# beeper.net
KiCad netlist of a schematic drawn in EAGLE
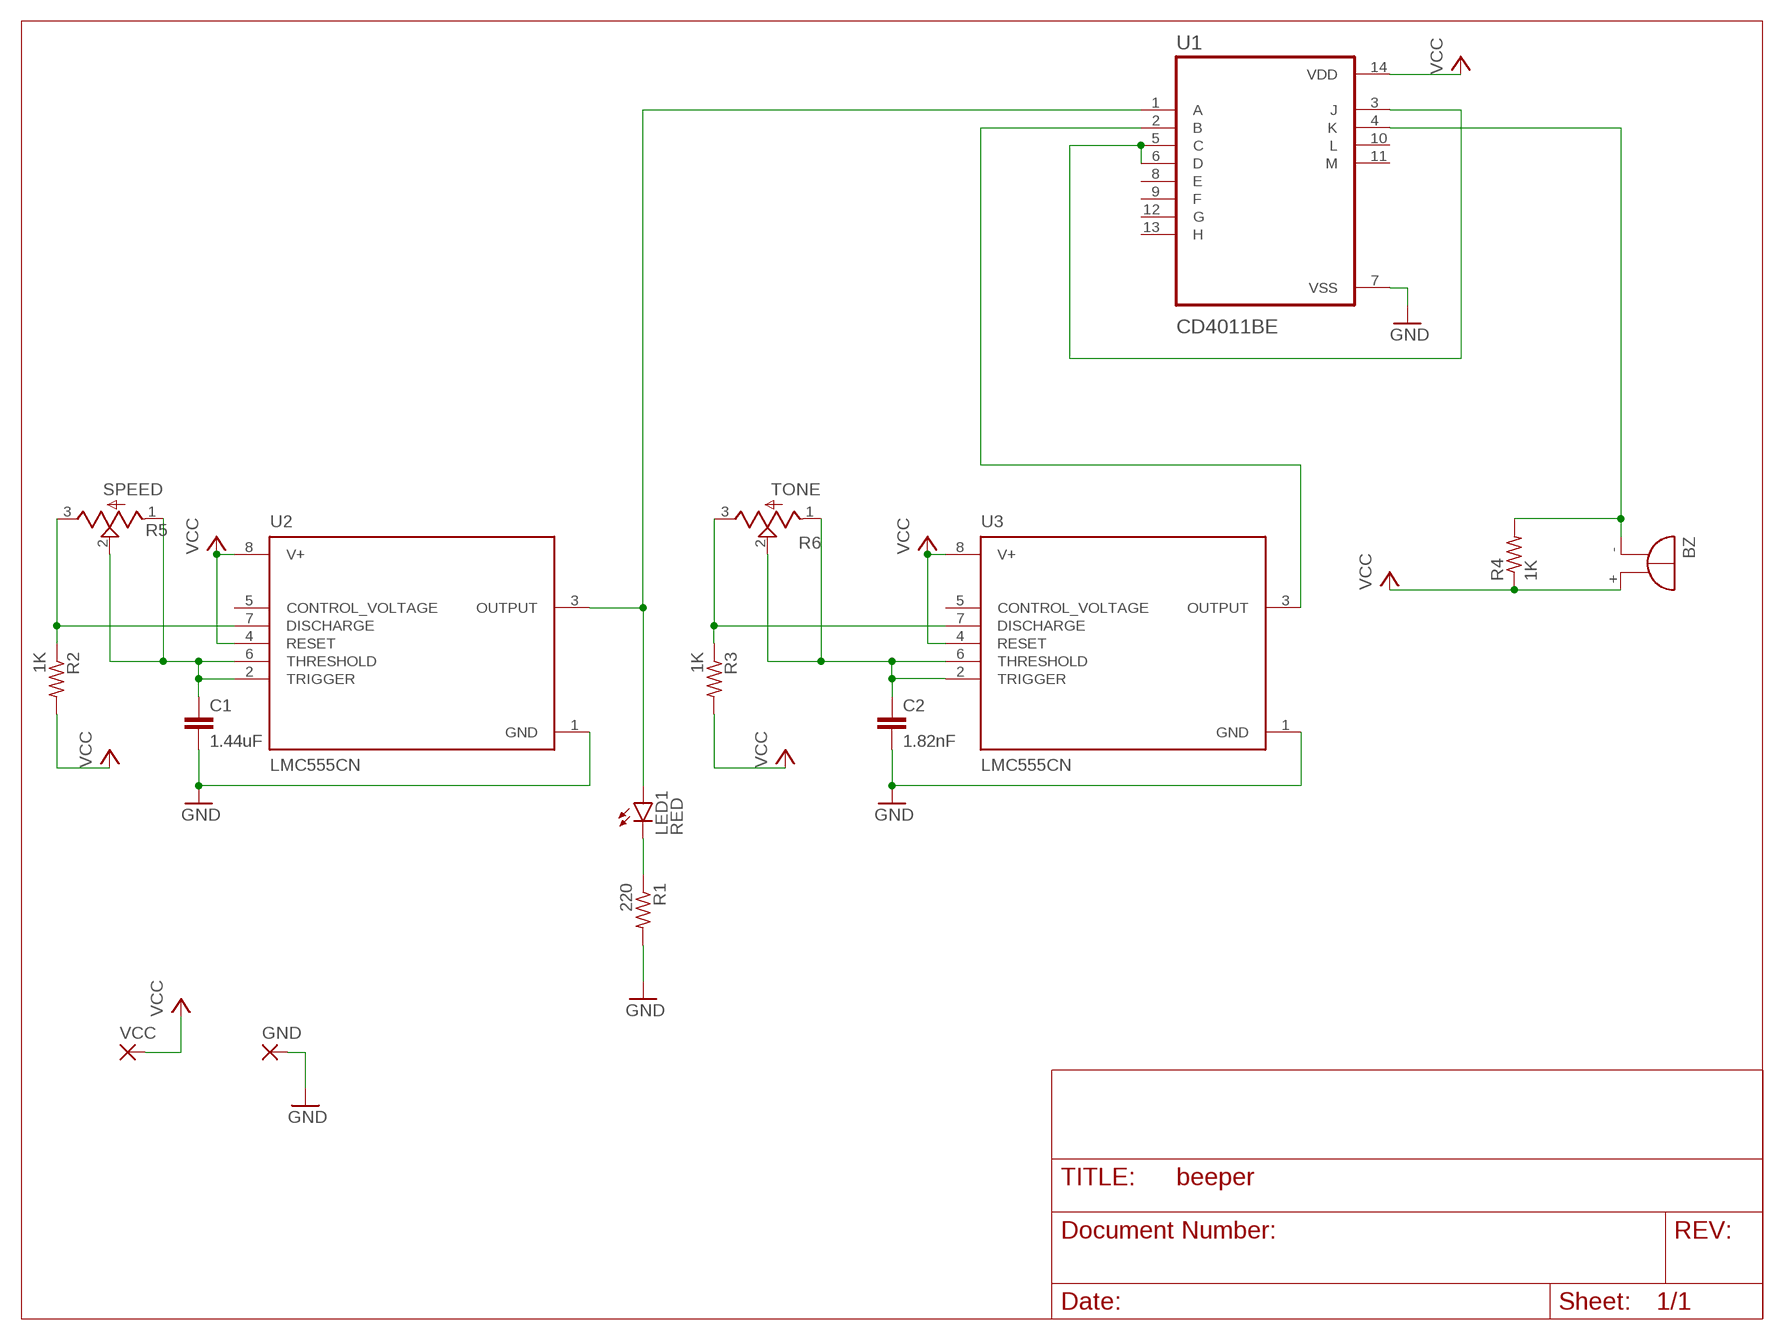
[diagram p0: schematic, sheet 1]

(export (version "E")
  (design (tool "Eeschema 10.0.6"))
  (components
    (comp (ref "BZ")
      (value "F/QMBIII")
      (footprint "eagle-import:F_QMBIII")
      (fields
        (field (name "MF") "PROJECTS UNLIMITED")
        (field (name "MPN") "AI-1440-TWT-12V-R")
        (field (name "OC_NEWARK") "47W0784")
      )
      (libsource (lib "eagle-import") (part "F/QMBIII"))
    )
    (comp (ref "C1")
      (value "1.44uF")
      (footprint "eagle-import:C2.5-3")
      (fields (field (name "MF") "MULTICOMP PRO") (field (name "MPN") "MPMPP250W15J0N200"))
      (libsource (lib "eagle-import") (part "C2,5-3"))
    )
    (comp (ref "C2")
      (value "1.82nF")
      (footprint "eagle-import:C2.5-3")
      (fields (field (name "MF") "TDK") (field (name "MPN") "FA26C0G2J182JNU00"))
      (libsource (lib "eagle-import") (part "C2,5-3"))
    )
    (comp (ref "GND")
      (value "SMD2")
      (footprint "eagle-import:SMD1,27-2,54")
      (libsource (lib "eagle-import") (part "SMD2"))
    )
    (comp (ref "LED1")
      (value "RED")
      (footprint "eagle-import:LED3MM")
      (fields
        (field (name "MF") "VISHAY SEMICONDUCTOR")
        (field (name "MF_1") "VISHAY")
        (field (name "MPN") "TLLR4400")
      )
      (libsource (lib "eagle-import") (part "TLLR4400"))
    )
    (comp (ref "R1")
      (value "220")
      (footprint "eagle-import:0204_7")
      (fields (field (name "MF") "MULTICOMP PRO") (field (name "MPN") "MCF 0.25W 220R"))
      (libsource (lib "eagle-import") (part "R-US_0204/7"))
    )
    (comp (ref "R2")
      (value "1K")
      (footprint "eagle-import:0204_7")
      (fields (field (name "MF") "MULTICOMP PRO") (field (name "MPN") "MP006904"))
      (libsource (lib "eagle-import") (part "R-US_0204/7"))
    )
    (comp (ref "R3")
      (value "1K")
      (footprint "eagle-import:0204_7")
      (fields (field (name "MF") "MULTICOMP PRO") (field (name "MPN") "MP006904"))
      (libsource (lib "eagle-import") (part "R-US_0204/7"))
    )
    (comp (ref "R4")
      (value "1K")
      (footprint "eagle-import:0204_7")
      (fields (field (name "MF") "MULTICOMP PRO") (field (name "MPN") "MP006904"))
      (libsource (lib "eagle-import") (part "R-US_0204/7"))
    )
    (comp (ref "R5")
      (value "SPEED")
      (footprint "eagle-import:TO250P760H635-3_PV12P105A01B00")
      (fields
        (field (name "MF") "Murata Electronics")
        (field (name "MP") "PV12P105A01B00")
        (field (name "MF_1") "BOURNS")
      )
      (libsource (lib "eagle-import") (part "PV12P105A01B00"))
    )
    (comp (ref "R6")
      (value "TONE")
      (footprint "eagle-import:TO250P760H635-3_PV12P105A01B00")
      (fields
        (field (name "MF") "Murata Electronics")
        (field (name "MP") "PV12P105A01B00")
        (field (name "MF_1") "BOURNS")
      )
      (libsource (lib "eagle-import") (part "PV12P105A01B00"))
    )
    (comp (ref "U1")
      (value "CD4011BE")
      (footprint "eagle-import:DIP794W45P254L1969H508Q14")
      (fields (field (name "MF") "Texas Instruments") (field (name "MF_1") "TEXAS INSTRUMENTS"))
      (libsource (lib "eagle-import") (part "CD4011BE"))
    )
    (comp (ref "U2")
      (value "LMC555CN")
      (footprint "eagle-import:DIP794W45P254L959H508Q8")
      (fields
        (field (name "MF") "Texas Instruments")
        (field (name "MF_1") "ONSEMI")
        (field (name "MPN") "LM555CN")
      )
      (libsource (lib "eagle-import") (part "LMC555CN"))
    )
    (comp (ref "U3")
      (value "LMC555CN")
      (footprint "eagle-import:DIP794W45P254L959H508Q8")
      (fields
        (field (name "MF") "Texas Instruments")
        (field (name "MF_1") "ONSEMI")
        (field (name "MPN") "LM555CN")
      )
      (libsource (lib "eagle-import") (part "LMC555CN"))
    )
    (comp (ref "VCC")
      (value "SMD2")
      (footprint "eagle-import:SMD1,27-2,54")
      (libsource (lib "eagle-import") (part "SMD2"))
    )
  )
  (nets
    (net (code "1") (name "GND") (class "Default")
      (node (ref "C1") (pin "2") (pinfunction "2_2") (pintype "passive"))
      (node (ref "C2") (pin "2") (pinfunction "2_2") (pintype "passive"))
      (node (ref "GND") (pin "1") (pinfunction "P_1") (pintype "passive"))
      (node (ref "R1") (pin "2") (pinfunction "2_2") (pintype "passive"))
      (node (ref "U1") (pin "7") (pinfunction "VSS_7") (pintype "power_in"))
      (node (ref "U2") (pin "1") (pinfunction "GND_1") (pintype "power_in"))
      (node (ref "U3") (pin "1") (pinfunction "GND_1") (pintype "power_in"))
    )
    (net (code "2") (name "Net-(BZ-+)") (class "Default")
      (node (ref "BZ") (pin "-") (pinfunction "+_-") (pintype "passive"))
      (node (ref "R4") (pin "2") (pinfunction "2_2") (pintype "passive"))
      (node (ref "U1") (pin "4") (pinfunction "K_4") (pintype "output"))
    )
    (net (code "3") (name "Net-(LED1-C)") (class "Default")
      (node (ref "LED1") (pin "K") (pinfunction "C_K") (pintype "passive"))
      (node (ref "R1") (pin "1") (pinfunction "1_1") (pintype "passive"))
    )
    (net (code "4") (name "Net-(U1-A)") (class "Default")
      (node (ref "LED1") (pin "A") (pinfunction "A_A") (pintype "passive"))
      (node (ref "U1") (pin "1") (pinfunction "A_1") (pintype "input"))
      (node (ref "U2") (pin "3") (pinfunction "OUTPUT_3") (pintype "output"))
    )
    (net (code "5") (name "Net-(U1-B)") (class "Default")
      (node (ref "U1") (pin "2") (pinfunction "B_2") (pintype "input"))
      (node (ref "U3") (pin "3") (pinfunction "OUTPUT_3") (pintype "output"))
    )
    (net (code "6") (name "Net-(U1-C)") (class "Default")
      (node (ref "U1") (pin "3") (pinfunction "J_3") (pintype "output"))
      (node (ref "U1") (pin "5") (pinfunction "C_5") (pintype "input"))
      (node (ref "U1") (pin "6") (pinfunction "D_6") (pintype "input"))
    )
    (net (code "7") (name "Net-(U2-DISCHARGE)") (class "Default")
      (node (ref "R2") (pin "1") (pinfunction "1_1") (pintype "passive"))
      (node (ref "R5") (pin "3") (pinfunction "3_3") (pintype "passive"))
      (node (ref "U2") (pin "7") (pinfunction "DISCHARGE_7") (pintype "input"))
    )
    (net (code "8") (name "Net-(U2-THRESHOLD)") (class "Default")
      (node (ref "C1") (pin "1") (pinfunction "1_1") (pintype "passive"))
      (node (ref "R5") (pin "1") (pinfunction "1_1") (pintype "passive"))
      (node (ref "R5") (pin "2") (pinfunction "2_2") (pintype "passive"))
      (node (ref "U2") (pin "2") (pinfunction "TRIGGER_2") (pintype "input"))
      (node (ref "U2") (pin "6") (pinfunction "THRESHOLD_6") (pintype "input"))
    )
    (net (code "9") (name "Net-(U3-DISCHARGE)") (class "Default")
      (node (ref "R3") (pin "1") (pinfunction "1_1") (pintype "passive"))
      (node (ref "R6") (pin "3") (pinfunction "3_3") (pintype "passive"))
      (node (ref "U3") (pin "7") (pinfunction "DISCHARGE_7") (pintype "input"))
    )
    (net (code "10") (name "Net-(U3-THRESHOLD)") (class "Default")
      (node (ref "C2") (pin "1") (pinfunction "1_1") (pintype "passive"))
      (node (ref "R6") (pin "1") (pinfunction "1_1") (pintype "passive"))
      (node (ref "R6") (pin "2") (pinfunction "2_2") (pintype "passive"))
      (node (ref "U3") (pin "2") (pinfunction "TRIGGER_2") (pintype "input"))
      (node (ref "U3") (pin "6") (pinfunction "THRESHOLD_6") (pintype "input"))
    )
    (net (code "11") (name "VCC") (class "Default")
      (node (ref "BZ") (pin "+") (pinfunction "-_+") (pintype "passive"))
      (node (ref "R2") (pin "2") (pinfunction "2_2") (pintype "passive"))
      (node (ref "R3") (pin "2") (pinfunction "2_2") (pintype "passive"))
      (node (ref "R4") (pin "1") (pinfunction "1_1") (pintype "passive"))
      (node (ref "U1") (pin "14") (pinfunction "VDD_14") (pintype "power_in"))
      (node (ref "U2") (pin "4") (pinfunction "RESET_4") (pintype "input"))
      (node (ref "U2") (pin "8") (pinfunction "V+_8") (pintype "power_in"))
      (node (ref "U3") (pin "4") (pinfunction "RESET_4") (pintype "input"))
      (node (ref "U3") (pin "8") (pinfunction "V+_8") (pintype "power_in"))
      (node (ref "VCC") (pin "1") (pinfunction "P_1") (pintype "passive"))
    )
    (net (code "12") (name "unconnected-(U1-E-Pad8)") (class "Default")
      (node (ref "U1") (pin "8") (pinfunction "E_8") (pintype "input"))
    )
    (net (code "13") (name "unconnected-(U1-F-Pad9)") (class "Default")
      (node (ref "U1") (pin "9") (pinfunction "F_9") (pintype "input"))
    )
    (net (code "14") (name "unconnected-(U1-G-Pad12)") (class "Default")
      (node (ref "U1") (pin "12") (pinfunction "G_12") (pintype "input"))
    )
    (net (code "15") (name "unconnected-(U1-H-Pad13)") (class "Default")
      (node (ref "U1") (pin "13") (pinfunction "H_13") (pintype "input"))
    )
    (net (code "16") (name "unconnected-(U1-L-Pad10)") (class "Default")
      (node (ref "U1") (pin "10") (pinfunction "L_10") (pintype "output"))
    )
    (net (code "17") (name "unconnected-(U1-M-Pad11)") (class "Default")
      (node (ref "U1") (pin "11") (pinfunction "M_11") (pintype "output"))
    )
    (net (code "18") (name "unconnected-(U2-CONTROL_VOLTAGE-Pad5)") (class "Default")
      (node (ref "U2") (pin "5") (pinfunction "CONTROL_VOLTAGE_5") (pintype "input"))
    )
    (net (code "19") (name "unconnected-(U3-CONTROL_VOLTAGE-Pad5)") (class "Default")
      (node (ref "U3") (pin "5") (pinfunction "CONTROL_VOLTAGE_5") (pintype "input"))
    )
  )
)
